# SCH_CyGarage.net
KiCad netlist of a schematic drawn in EasyEDA
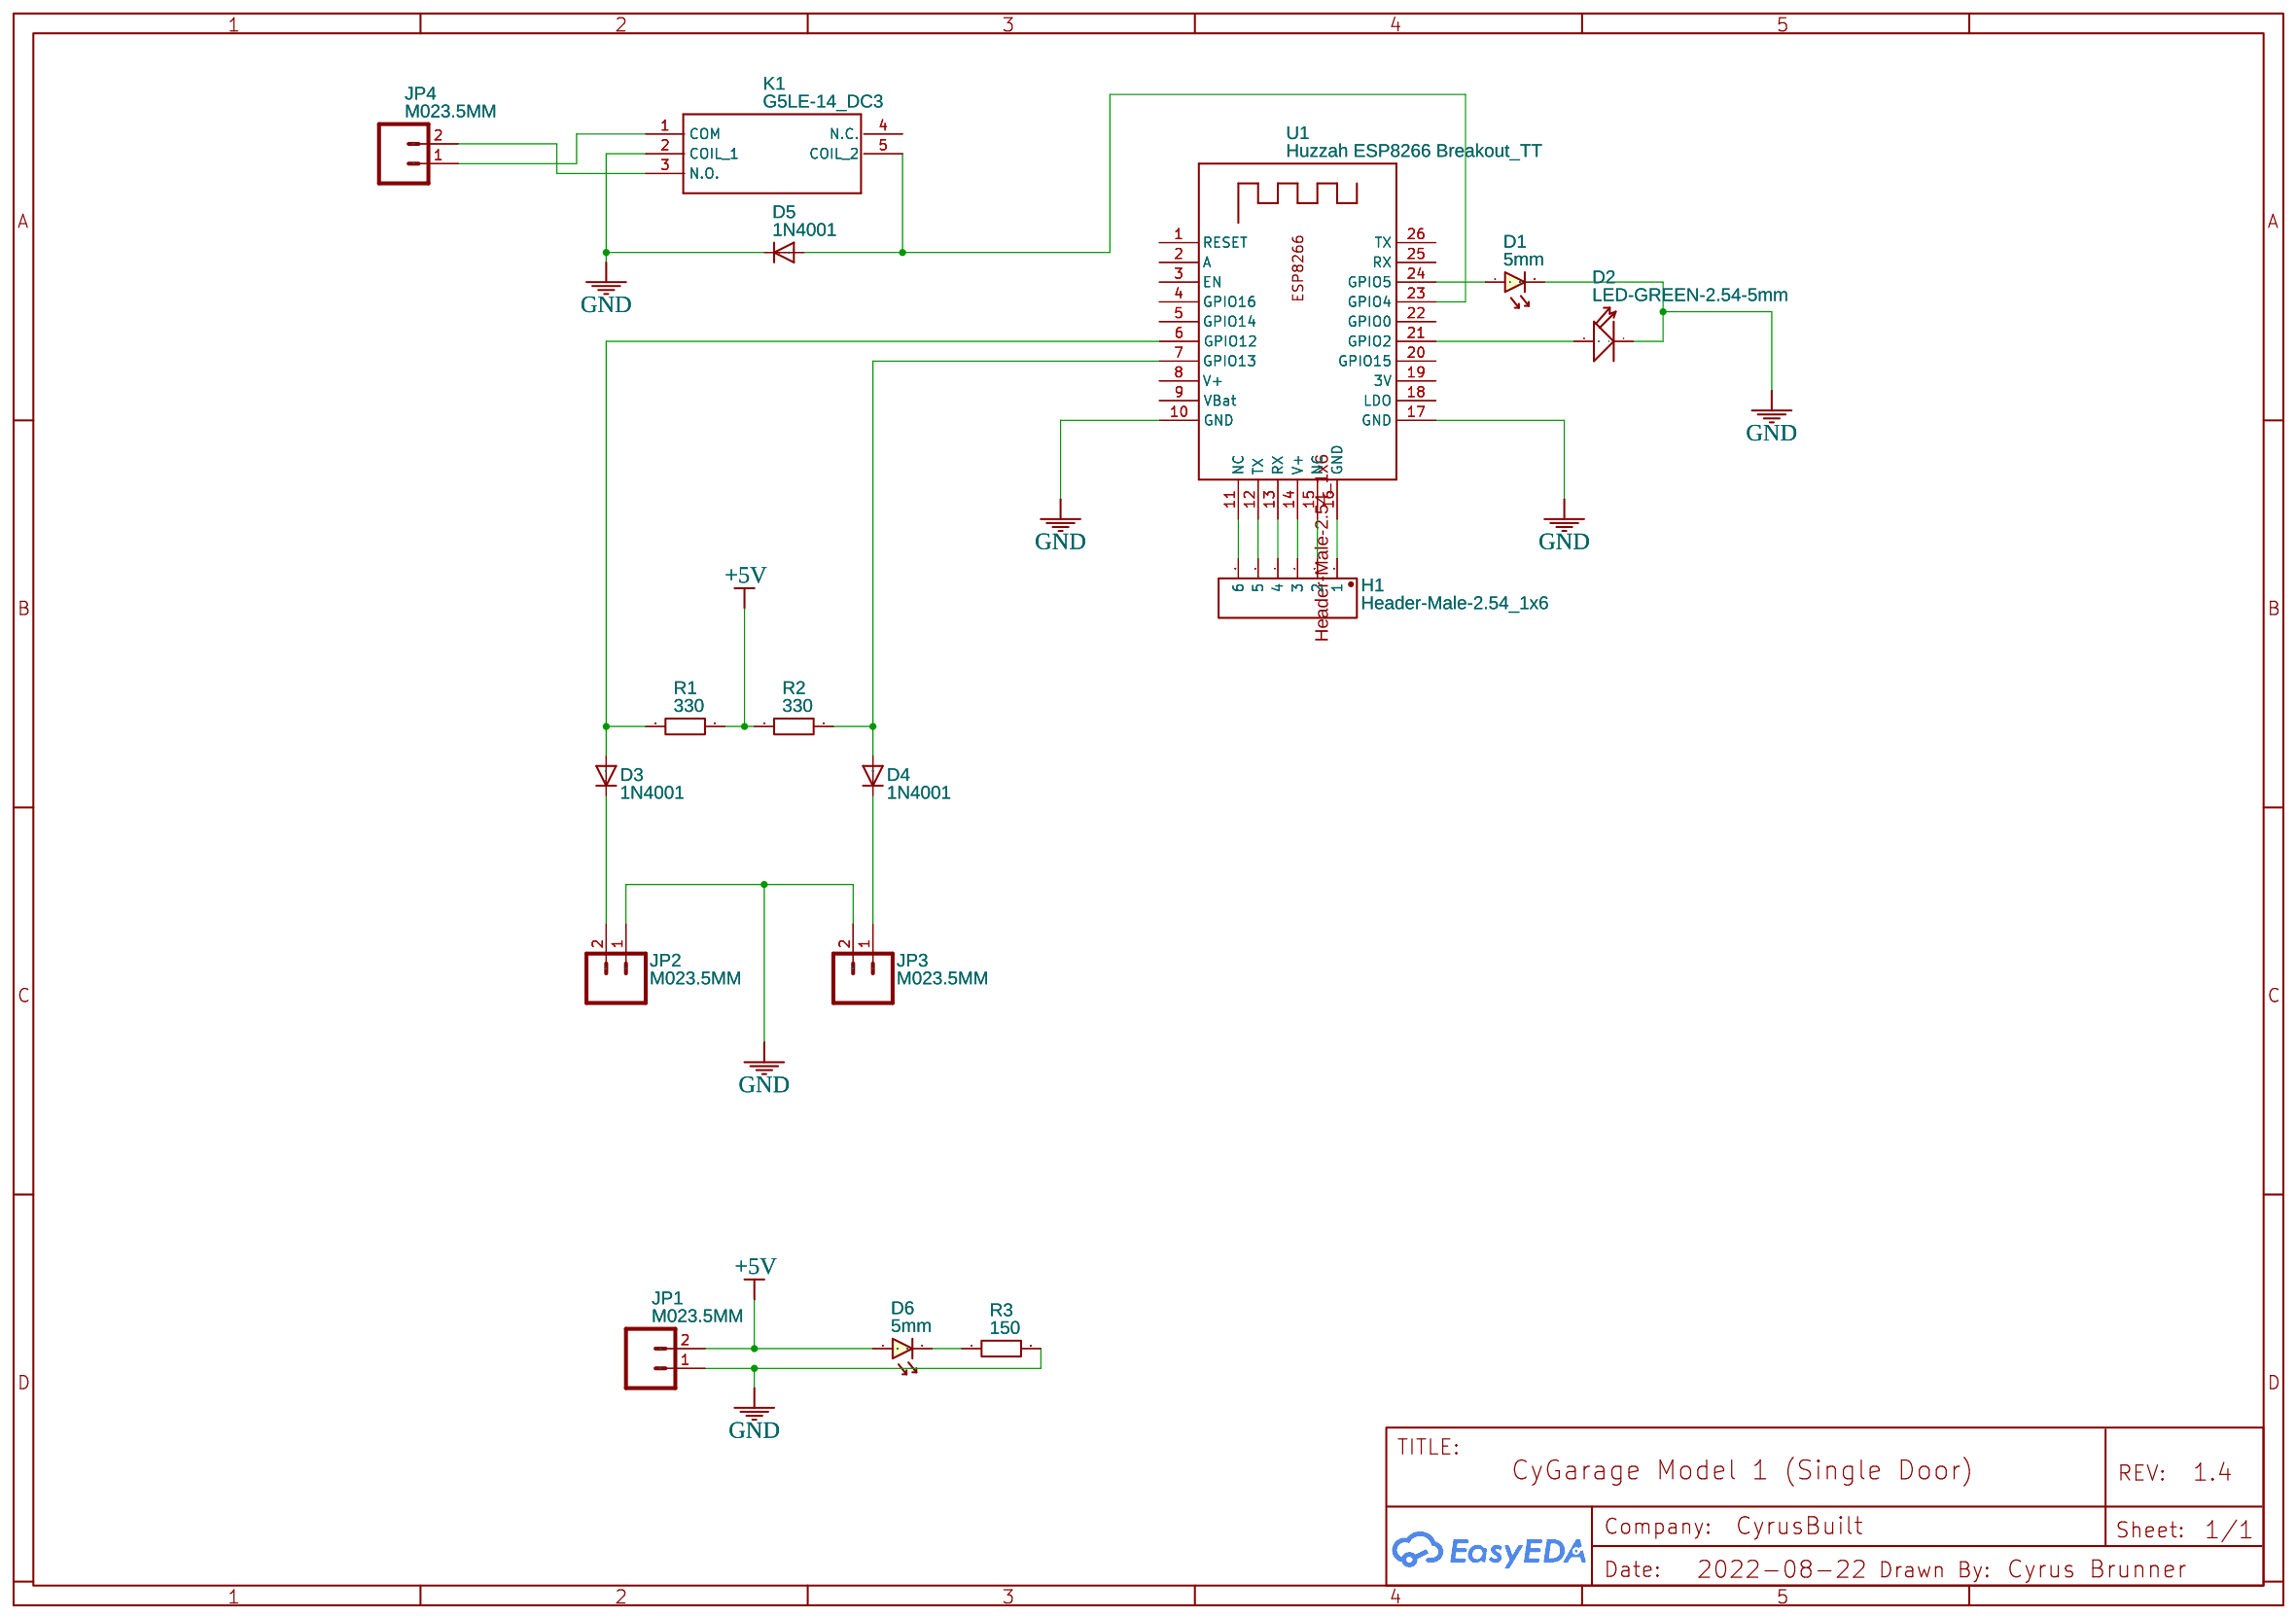
[diagram p0: schematic sheet]

(export (version "E")
  (design (tool "Eeschema 10.0.6"))
  (components
    (comp (ref "D1")
      (value "5mm")
      (fields (field (name "BOM_Manufacturer Part") "L-1503EC") (field (name "BOM_Supplier Part") "1003201"))
      (libsource (lib "") (part "L-1503EC"))
    )
    (comp (ref "D2")
      (value "LED-GREEN-2.54-5mm")
      (fields (field (name "BOM_Manufacturer Part") "503UOC"))
      (libsource (lib "") (part "LED-GREEN-2.54-5mm"))
    )
    (comp (ref "D3") (value "1N4001") (libsource (lib "") (part "1N4001")))
    (comp (ref "D4") (value "1N4001") (libsource (lib "") (part "1N4001")))
    (comp (ref "D5") (value "1N4001") (libsource (lib "") (part "1N4001_1")))
    (comp (ref "D6")
      (value "5mm")
      (fields (field (name "BOM_Manufacturer Part") "L-1503EC") (field (name "BOM_Supplier Part") "1003201"))
      (libsource (lib "") (part "L-1503EC"))
    )
    (comp (ref "H1") (value "Header-Male-2.54_1x6") (libsource (lib "") (part "Header-Male-2.54_1x6")))
    (comp (ref "JP1") (value "M023.5MM") (libsource (lib "") (part "M023.5MM")))
    (comp (ref "JP2") (value "M023.5MM") (libsource (lib "") (part "M023.5MM_1")))
    (comp (ref "JP3") (value "M023.5MM") (libsource (lib "") (part "M023.5MM_1")))
    (comp (ref "JP4") (value "M023.5MM") (libsource (lib "") (part "M023.5MM")))
    (comp (ref "K1") (value "G5LE-14_DC3") (libsource (lib "") (part "G5LE-14_DC3")))
    (comp (ref "R1") (value "330") (libsource (lib "") (part "330")))
    (comp (ref "R2") (value "330") (libsource (lib "") (part "330")))
    (comp (ref "R3") (value "150") (libsource (lib "") (part "150")))
    (comp (ref "U1")
      (value "Huzzah ESP8266 Breakout_TT")
      (libsource (lib "") (part "Huzzah ESP8266 Breakout_TT"))
    )
  )
  (nets
    (net (code "1") (name "+5V") (class "Default")
      (node (ref "D6") (pin "1") (pinfunction "1_1") (pintype "unspecified"))
      (node (ref "JP1") (pin "2") (pinfunction "2_2") (pintype "unspecified"))
      (node (ref "R1") (pin "2") (pintype "unspecified"))
      (node (ref "R2") (pin "1") (pintype "unspecified"))
    )
    (net (code "2") (name "GND") (class "Default")
      (node (ref "D1") (pin "2") (pinfunction "2_2") (pintype "unspecified"))
      (node (ref "D2") (pin "-") (pinfunction "-_-") (pintype "unspecified"))
      (node (ref "D5") (pin "C") (pinfunction "C_C") (pintype "unspecified"))
      (node (ref "JP1") (pin "1") (pinfunction "1_1") (pintype "unspecified"))
      (node (ref "JP2") (pin "1") (pinfunction "1_1") (pintype "unspecified"))
      (node (ref "JP3") (pin "2") (pinfunction "2_2") (pintype "unspecified"))
      (node (ref "K1") (pin "2") (pinfunction "COIL_1_2") (pintype "bidirectional"))
      (node (ref "R3") (pin "2") (pintype "unspecified"))
      (node (ref "U1") (pin "10") (pinfunction "GND_10") (pintype "unspecified"))
      (node (ref "U1") (pin "17") (pinfunction "GND_17") (pintype "unspecified"))
    )
    (net (code "3") (name "Net-(D3-PadC)") (class "Default")
      (node (ref "D3") (pin "C") (pinfunction "C_C") (pintype "unspecified"))
      (node (ref "JP2") (pin "2") (pinfunction "2_2") (pintype "unspecified"))
    )
    (net (code "4") (name "Net-(D4-PadC)") (class "Default")
      (node (ref "D4") (pin "C") (pinfunction "C_C") (pintype "unspecified"))
      (node (ref "JP3") (pin "1") (pinfunction "1_1") (pintype "unspecified"))
    )
    (net (code "5") (name "Net-(D6-Pad2)") (class "Default")
      (node (ref "D6") (pin "2") (pinfunction "2_2") (pintype "unspecified"))
      (node (ref "R3") (pin "1") (pintype "unspecified"))
    )
    (net (code "6") (name "Net-(H1-Pad1)") (class "Default")
      (node (ref "H1") (pin "1") (pinfunction "1_1") (pintype "unspecified"))
      (node (ref "U1") (pin "16") (pinfunction "GND_16") (pintype "unspecified"))
    )
    (net (code "7") (name "Net-(H1-Pad2)") (class "Default")
      (node (ref "H1") (pin "2") (pinfunction "2_2") (pintype "unspecified"))
      (node (ref "U1") (pin "15") (pinfunction "NC_15") (pintype "unspecified"))
    )
    (net (code "8") (name "Net-(H1-Pad3)") (class "Default")
      (node (ref "H1") (pin "3") (pinfunction "3_3") (pintype "unspecified"))
      (node (ref "U1") (pin "14") (pinfunction "V+_14") (pintype "unspecified"))
    )
    (net (code "9") (name "Net-(H1-Pad4)") (class "Default")
      (node (ref "H1") (pin "4") (pinfunction "4_4") (pintype "unspecified"))
      (node (ref "U1") (pin "13") (pinfunction "RX_13") (pintype "unspecified"))
    )
    (net (code "10") (name "Net-(H1-Pad5)") (class "Default")
      (node (ref "H1") (pin "5") (pinfunction "5_5") (pintype "unspecified"))
      (node (ref "U1") (pin "12") (pinfunction "TX_12") (pintype "unspecified"))
    )
    (net (code "11") (name "Net-(H1-Pad6)") (class "Default")
      (node (ref "H1") (pin "6") (pinfunction "6_6") (pintype "unspecified"))
      (node (ref "U1") (pin "11") (pinfunction "NC_11") (pintype "unspecified"))
    )
    (net (code "12") (name "Net-(K1-COIL_2)") (class "Default")
      (node (ref "D5") (pin "A") (pinfunction "A_A") (pintype "unspecified"))
      (node (ref "K1") (pin "5") (pinfunction "COIL_2_5") (pintype "bidirectional"))
      (node (ref "U1") (pin "23") (pinfunction "GPIO4_23") (pintype "bidirectional"))
    )
    (net (code "13") (name "Net-(K1-COM)") (class "Default")
      (node (ref "JP4") (pin "1") (pinfunction "1_1") (pintype "unspecified"))
      (node (ref "K1") (pin "1") (pinfunction "COM_1") (pintype "bidirectional"))
    )
    (net (code "14") (name "Net-(K1-N.O.)") (class "Default")
      (node (ref "JP4") (pin "2") (pinfunction "2_2") (pintype "unspecified"))
      (node (ref "K1") (pin "3") (pinfunction "N.O._3") (pintype "bidirectional"))
    )
    (net (code "15") (name "Net-(U1-GPIO2)") (class "Default")
      (node (ref "D2") (pin "+") (pinfunction "+_+") (pintype "unspecified"))
      (node (ref "U1") (pin "21") (pinfunction "GPIO2_21") (pintype "bidirectional"))
    )
    (net (code "16") (name "Net-(U1-GPIO5)") (class "Default")
      (node (ref "D1") (pin "1") (pinfunction "1_1") (pintype "unspecified"))
      (node (ref "U1") (pin "24") (pinfunction "GPIO5_24") (pintype "bidirectional"))
    )
    (net (code "17") (name "Net-(U1-GPIO12)") (class "Default")
      (node (ref "D3") (pin "A") (pinfunction "A_A") (pintype "unspecified"))
      (node (ref "R1") (pin "1") (pintype "unspecified"))
      (node (ref "U1") (pin "6") (pinfunction "GPIO12_6") (pintype "unspecified"))
    )
    (net (code "18") (name "Net-(U1-GPIO13)") (class "Default")
      (node (ref "D4") (pin "A") (pinfunction "A_A") (pintype "unspecified"))
      (node (ref "R2") (pin "2") (pintype "unspecified"))
      (node (ref "U1") (pin "7") (pinfunction "GPIO13_7") (pintype "bidirectional"))
    )
    (net (code "19") (name "unconnected-(K1-N.C.-Pad4)") (class "Default")
      (node (ref "K1") (pin "4") (pinfunction "N.C._4") (pintype "bidirectional"))
    )
    (net (code "20") (name "unconnected-(U1-3V-Pad19)") (class "Default")
      (node (ref "U1") (pin "19") (pinfunction "3V_19") (pintype "unspecified"))
    )
    (net (code "21") (name "unconnected-(U1-A-Pad2)") (class "Default")
      (node (ref "U1") (pin "2") (pinfunction "A_2") (pintype "bidirectional"))
    )
    (net (code "22") (name "unconnected-(U1-EN-Pad3)") (class "Default")
      (node (ref "U1") (pin "3") (pinfunction "EN_3") (pintype "bidirectional"))
    )
    (net (code "23") (name "unconnected-(U1-GPIO0-Pad22)") (class "Default")
      (node (ref "U1") (pin "22") (pinfunction "GPIO0_22") (pintype "bidirectional"))
    )
    (net (code "24") (name "unconnected-(U1-GPIO14-Pad5)") (class "Default")
      (node (ref "U1") (pin "5") (pinfunction "GPIO14_5") (pintype "bidirectional"))
    )
    (net (code "25") (name "unconnected-(U1-GPIO15-Pad20)") (class "Default")
      (node (ref "U1") (pin "20") (pinfunction "GPIO15_20") (pintype "bidirectional"))
    )
    (net (code "26") (name "unconnected-(U1-GPIO16-Pad4)") (class "Default")
      (node (ref "U1") (pin "4") (pinfunction "GPIO16_4") (pintype "bidirectional"))
    )
    (net (code "27") (name "unconnected-(U1-LDO-Pad18)") (class "Default")
      (node (ref "U1") (pin "18") (pinfunction "LDO_18") (pintype "unspecified"))
    )
    (net (code "28") (name "unconnected-(U1-RESET-Pad1)") (class "Default")
      (node (ref "U1") (pin "1") (pinfunction "RESET_1") (pintype "bidirectional"))
    )
    (net (code "29") (name "unconnected-(U1-RX-Pad25)") (class "Default")
      (node (ref "U1") (pin "25") (pinfunction "RX_25") (pintype "bidirectional"))
    )
    (net (code "30") (name "unconnected-(U1-TX-Pad26)") (class "Default")
      (node (ref "U1") (pin "26") (pinfunction "TX_26") (pintype "bidirectional"))
    )
    (net (code "31") (name "unconnected-(U1-V+-Pad8)") (class "Default")
      (node (ref "U1") (pin "8") (pinfunction "V+_8") (pintype "bidirectional"))
    )
    (net (code "32") (name "unconnected-(U1-VBat-Pad9)") (class "Default")
      (node (ref "U1") (pin "9") (pinfunction "VBat_9") (pintype "unspecified"))
    )
  )
)
